# Sheet1.net
KiCad netlist of a schematic drawn in Altium Designer
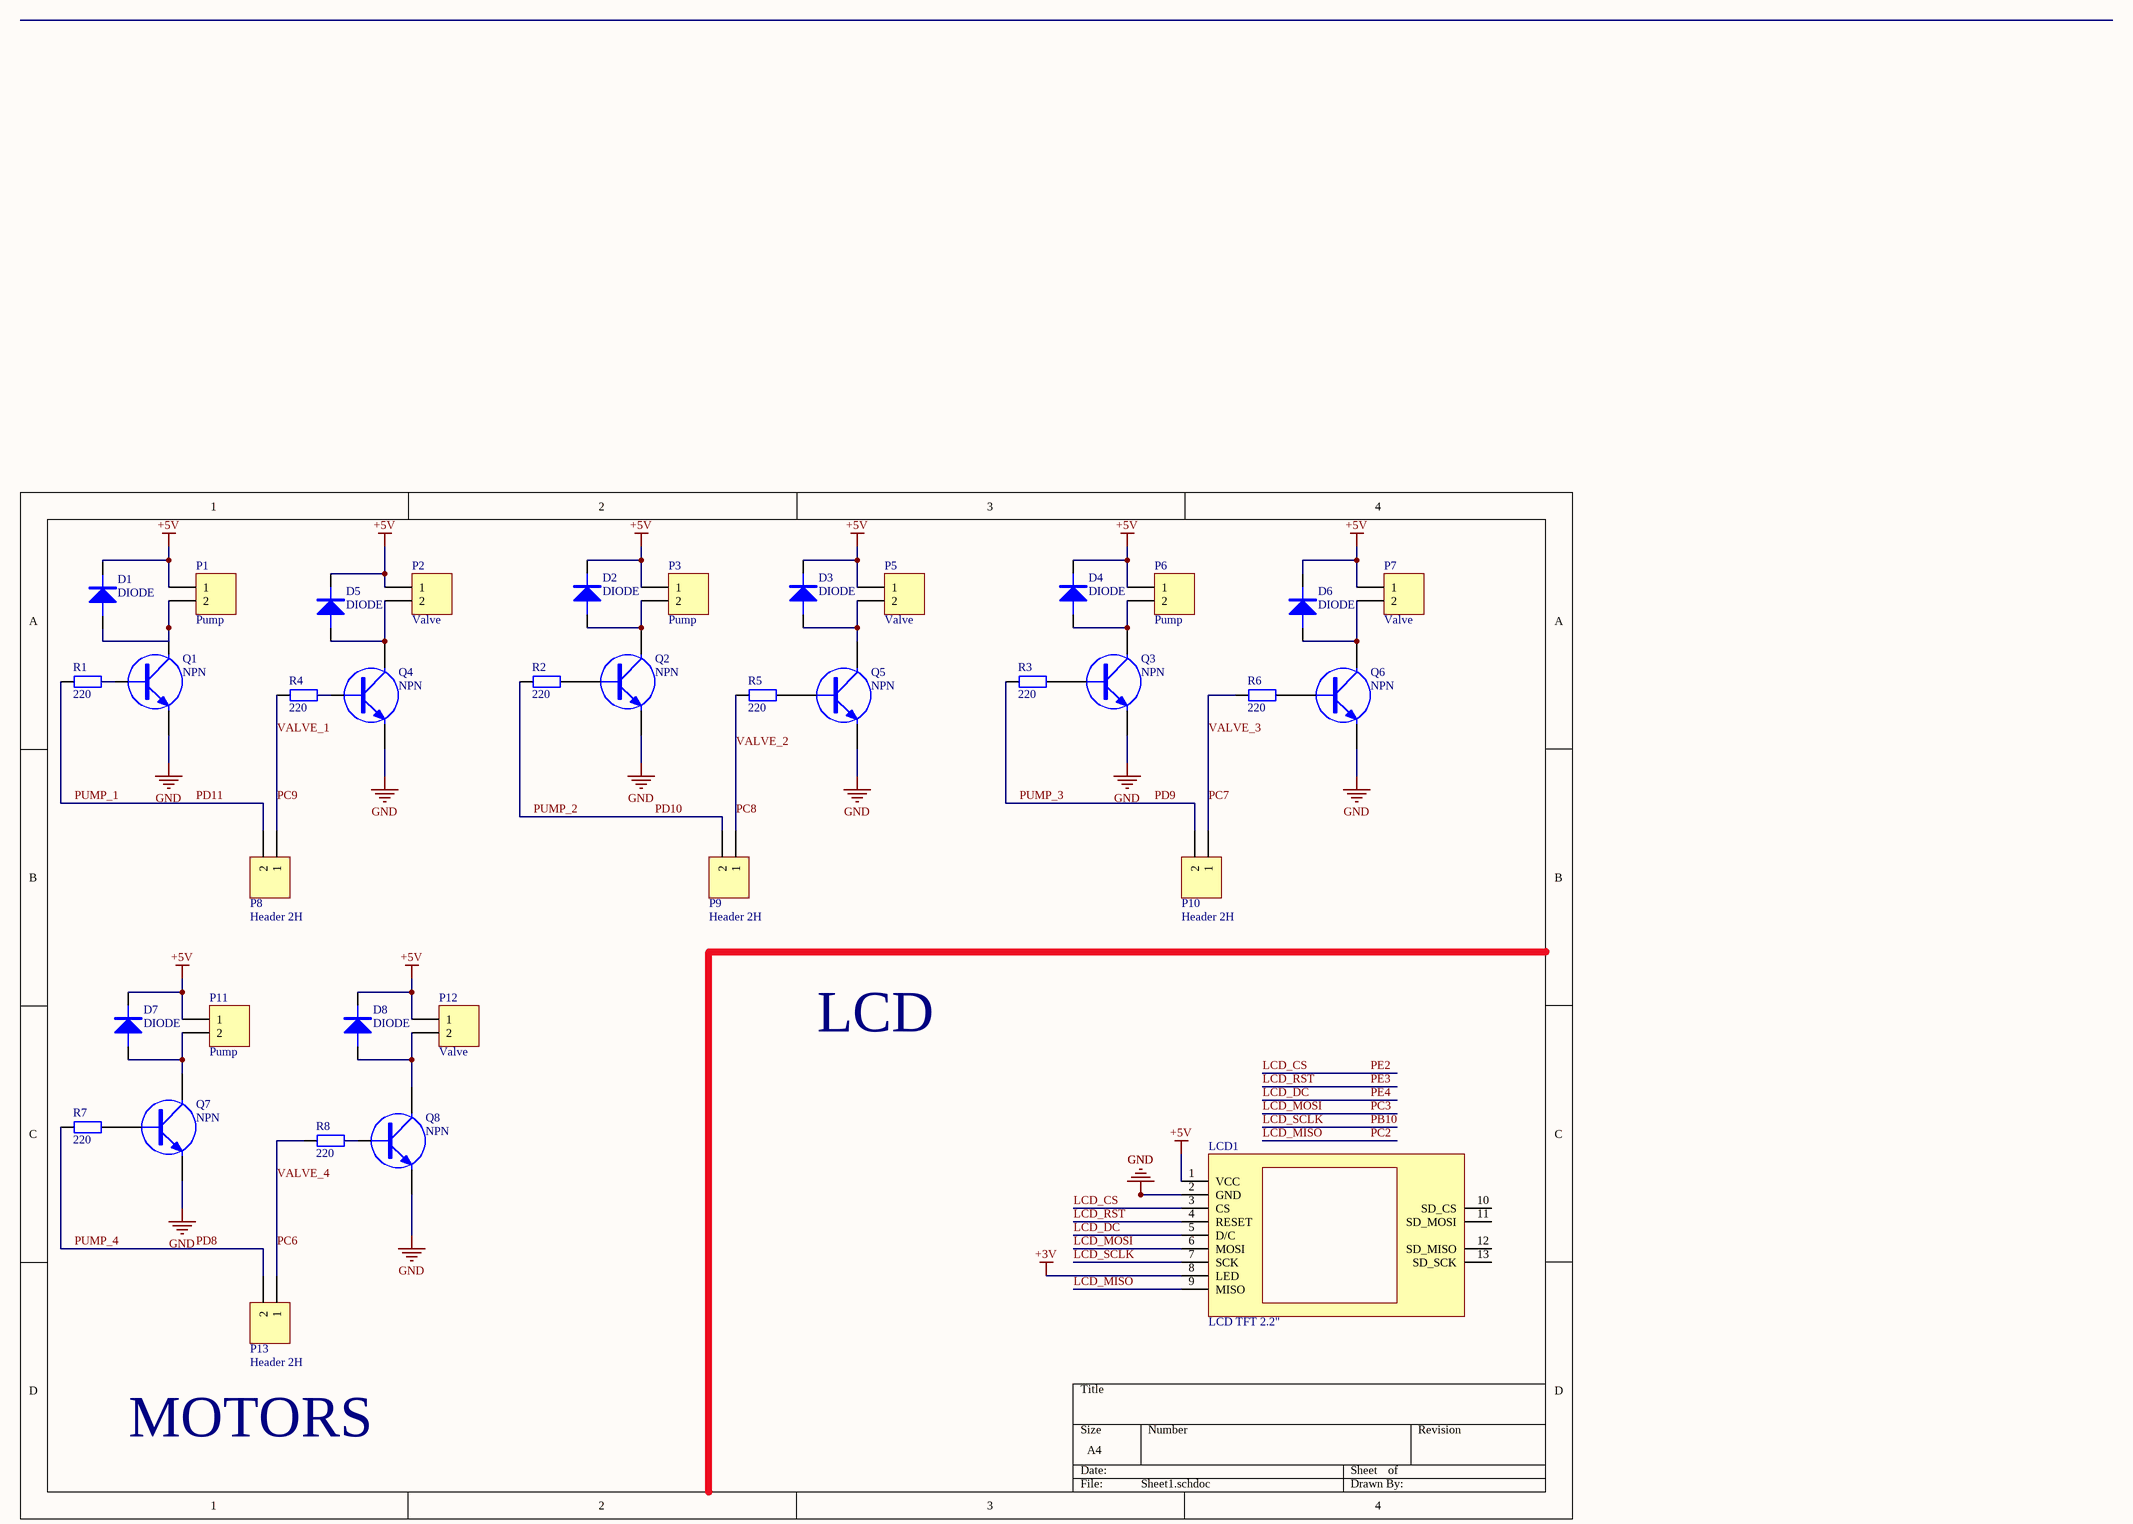
[diagram p0: Sheet1.schdoc]

(export (version "E")
  (design (tool "Eeschema 10.0.6"))
  (components
    (comp (ref "D1")
      (value "DIODE")
      (footprint "DIODE SMA")
      (libsource (lib "ThinhNguyenLib") (part "DIODE"))
    )
    (comp (ref "D2")
      (value "DIODE")
      (footprint "DIODE SMA")
      (libsource (lib "ThinhNguyenLib") (part "DIODE"))
    )
    (comp (ref "D3")
      (value "DIODE")
      (footprint "DIODE SMA")
      (libsource (lib "ThinhNguyenLib") (part "DIODE"))
    )
    (comp (ref "D4")
      (value "DIODE")
      (footprint "DIODE SMA")
      (libsource (lib "ThinhNguyenLib") (part "DIODE"))
    )
    (comp (ref "D5")
      (value "DIODE")
      (footprint "DIODE SMA")
      (libsource (lib "ThinhNguyenLib") (part "DIODE"))
    )
    (comp (ref "D6")
      (value "DIODE")
      (footprint "DIODE SMA")
      (libsource (lib "ThinhNguyenLib") (part "DIODE"))
    )
    (comp (ref "D7")
      (value "DIODE")
      (footprint "DIODE SMA")
      (libsource (lib "ThinhNguyenLib") (part "DIODE"))
    )
    (comp (ref "D8")
      (value "DIODE")
      (footprint "DIODE SMA")
      (libsource (lib "ThinhNguyenLib") (part "DIODE"))
    )
    (comp (ref "LCD1")
      (value "LCD TFT 2.2\"")
      (footprint "LCD TFT 2.2\"")
      (libsource (lib "ThinhNguyenLib") (part "LCD TFT 2.2{dblquote}"))
    )
    (comp (ref "P1")
      (value "Pump")
      (footprint "HDR1X2")
      (fields (field (name "PUBLISHER") "Altium Limited"))
      (libsource (lib "ThinhNguyenLib") (part "Header 2H"))
    )
    (comp (ref "P2")
      (value "Valve")
      (footprint "HDR1X2")
      (fields (field (name "PUBLISHER") "Altium Limited"))
      (libsource (lib "ThinhNguyenLib") (part "Header 2H"))
    )
    (comp (ref "P3")
      (value "Pump")
      (footprint "HDR1X2")
      (fields (field (name "PUBLISHER") "Altium Limited"))
      (libsource (lib "ThinhNguyenLib") (part "Header 2H"))
    )
    (comp (ref "P5")
      (value "Valve")
      (footprint "HDR1X2")
      (fields (field (name "PUBLISHER") "Altium Limited"))
      (libsource (lib "ThinhNguyenLib") (part "Header 2H"))
    )
    (comp (ref "P6")
      (value "Pump")
      (footprint "HDR1X2")
      (fields (field (name "PUBLISHER") "Altium Limited"))
      (libsource (lib "ThinhNguyenLib") (part "Header 2H"))
    )
    (comp (ref "P7")
      (value "Valve")
      (footprint "HDR1X2")
      (fields (field (name "PUBLISHER") "Altium Limited"))
      (libsource (lib "ThinhNguyenLib") (part "Header 2H"))
    )
    (comp (ref "P8")
      (value "Header 2H")
      (footprint "HDR1X2")
      (fields (field (name "PUBLISHER") "Altium Limited"))
      (libsource (lib "") (part "Header 2H_1"))
    )
    (comp (ref "P9")
      (value "Header 2H")
      (footprint "HDR1X2")
      (fields (field (name "PUBLISHER") "Altium Limited"))
      (libsource (lib "") (part "Header 2H_1"))
    )
    (comp (ref "P10")
      (value "Header 2H")
      (footprint "HDR1X2")
      (fields (field (name "PUBLISHER") "Altium Limited"))
      (libsource (lib "") (part "Header 2H_1"))
    )
    (comp (ref "P11")
      (value "Pump")
      (footprint "HDR1X2")
      (fields (field (name "PUBLISHER") "Altium Limited"))
      (libsource (lib "ThinhNguyenLib") (part "Header 2H"))
    )
    (comp (ref "P12")
      (value "Valve")
      (footprint "HDR1X2")
      (fields (field (name "PUBLISHER") "Altium Limited"))
      (libsource (lib "ThinhNguyenLib") (part "Header 2H"))
    )
    (comp (ref "P13")
      (value "Header 2H")
      (footprint "HDR1X2")
      (fields (field (name "PUBLISHER") "Altium Limited"))
      (libsource (lib "") (part "Header 2H_1"))
    )
    (comp (ref "Q1") (value "NPN") (footprint "SOT23 - 3PIN") (libsource (lib "ThinhNguyenLib") (part "NPN")))
    (comp (ref "Q2") (value "NPN") (footprint "SOT23 - 3PIN") (libsource (lib "ThinhNguyenLib") (part "NPN")))
    (comp (ref "Q3") (value "NPN") (footprint "SOT23 - 3PIN") (libsource (lib "ThinhNguyenLib") (part "NPN")))
    (comp (ref "Q4") (value "NPN") (footprint "SOT23 - 3PIN") (libsource (lib "ThinhNguyenLib") (part "NPN")))
    (comp (ref "Q5") (value "NPN") (footprint "SOT23 - 3PIN") (libsource (lib "ThinhNguyenLib") (part "NPN")))
    (comp (ref "Q6") (value "NPN") (footprint "SOT23 - 3PIN") (libsource (lib "ThinhNguyenLib") (part "NPN")))
    (comp (ref "Q7") (value "NPN") (footprint "SOT23 - 3PIN") (libsource (lib "ThinhNguyenLib") (part "NPN")))
    (comp (ref "Q8") (value "NPN") (footprint "SOT23 - 3PIN") (libsource (lib "ThinhNguyenLib") (part "NPN")))
    (comp (ref "R1")
      (value "220")
      (footprint "0805 RESISTOR")
      (libsource (lib "ThinhNguyenLib") (part "RESISTOR"))
    )
    (comp (ref "R2")
      (value "220")
      (footprint "0805 RESISTOR")
      (libsource (lib "ThinhNguyenLib") (part "RESISTOR"))
    )
    (comp (ref "R3")
      (value "220")
      (footprint "0805 RESISTOR")
      (libsource (lib "ThinhNguyenLib") (part "RESISTOR"))
    )
    (comp (ref "R4")
      (value "220")
      (footprint "0805 RESISTOR")
      (libsource (lib "ThinhNguyenLib") (part "RESISTOR"))
    )
    (comp (ref "R5")
      (value "220")
      (footprint "0805 RESISTOR")
      (libsource (lib "ThinhNguyenLib") (part "RESISTOR"))
    )
    (comp (ref "R6")
      (value "220")
      (footprint "0805 RESISTOR")
      (libsource (lib "ThinhNguyenLib") (part "RESISTOR"))
    )
    (comp (ref "R7")
      (value "220")
      (footprint "0805 RESISTOR")
      (libsource (lib "ThinhNguyenLib") (part "RESISTOR"))
    )
    (comp (ref "R8")
      (value "220")
      (footprint "0805 RESISTOR")
      (libsource (lib "ThinhNguyenLib") (part "RESISTOR"))
    )
  )
  (nets
    (net (code "1") (name "+3V") (class "Default")
      (node (ref "LCD1") (pin "8") (pinfunction "LED_8") (pintype "passive"))
    )
    (net (code "2") (name "+5V") (class "Default")
      (node (ref "D1") (pin "2") (pinfunction "2_2") (pintype "passive"))
      (node (ref "D2") (pin "2") (pinfunction "2_2") (pintype "passive"))
      (node (ref "D3") (pin "2") (pinfunction "2_2") (pintype "passive"))
      (node (ref "D4") (pin "2") (pinfunction "2_2") (pintype "passive"))
      (node (ref "D5") (pin "2") (pinfunction "2_2") (pintype "passive"))
      (node (ref "D6") (pin "2") (pinfunction "2_2") (pintype "passive"))
      (node (ref "D7") (pin "2") (pinfunction "2_2") (pintype "passive"))
      (node (ref "D8") (pin "2") (pinfunction "2_2") (pintype "passive"))
      (node (ref "LCD1") (pin "1") (pinfunction "VCC_1") (pintype "passive"))
      (node (ref "P1") (pin "1") (pinfunction "1_1") (pintype "passive"))
      (node (ref "P11") (pin "1") (pinfunction "1_1") (pintype "passive"))
      (node (ref "P12") (pin "1") (pinfunction "1_1") (pintype "passive"))
      (node (ref "P2") (pin "1") (pinfunction "1_1") (pintype "passive"))
      (node (ref "P3") (pin "1") (pinfunction "1_1") (pintype "passive"))
      (node (ref "P5") (pin "1") (pinfunction "1_1") (pintype "passive"))
      (node (ref "P6") (pin "1") (pinfunction "1_1") (pintype "passive"))
      (node (ref "P7") (pin "1") (pinfunction "1_1") (pintype "passive"))
    )
    (net (code "3") (name "/LCD_CS") (class "Default")
      (node (ref "LCD1") (pin "3") (pinfunction "CS_3") (pintype "passive"))
    )
    (net (code "4") (name "/LCD_DC") (class "Default")
      (node (ref "LCD1") (pin "5") (pinfunction "D/C_5") (pintype "passive"))
    )
    (net (code "5") (name "/LCD_MISO") (class "Default")
      (node (ref "LCD1") (pin "9") (pinfunction "MISO_9") (pintype "passive"))
    )
    (net (code "6") (name "/LCD_MOSI") (class "Default")
      (node (ref "LCD1") (pin "6") (pinfunction "MOSI_6") (pintype "passive"))
    )
    (net (code "7") (name "/LCD_RST") (class "Default")
      (node (ref "LCD1") (pin "4") (pinfunction "RESET_4") (pintype "passive"))
    )
    (net (code "8") (name "/LCD_SCLK") (class "Default")
      (node (ref "LCD1") (pin "7") (pinfunction "SCK_7") (pintype "passive"))
    )
    (net (code "9") (name "/PC6") (class "Default")
      (node (ref "P13") (pin "1") (pinfunction "1_1") (pintype "passive"))
      (node (ref "R8") (pin "2") (pinfunction "2_2") (pintype "passive"))
    )
    (net (code "10") (name "/PC7") (class "Default")
      (node (ref "P10") (pin "1") (pinfunction "1_1") (pintype "passive"))
      (node (ref "R6") (pin "2") (pinfunction "2_2") (pintype "passive"))
    )
    (net (code "11") (name "/PC8") (class "Default")
      (node (ref "P9") (pin "1") (pinfunction "1_1") (pintype "passive"))
      (node (ref "R5") (pin "2") (pinfunction "2_2") (pintype "passive"))
    )
    (net (code "12") (name "/PC9") (class "Default")
      (node (ref "P8") (pin "1") (pinfunction "1_1") (pintype "passive"))
      (node (ref "R4") (pin "2") (pinfunction "2_2") (pintype "passive"))
    )
    (net (code "13") (name "/PD8") (class "Default")
      (node (ref "P13") (pin "2") (pinfunction "2_2") (pintype "passive"))
      (node (ref "R7") (pin "2") (pinfunction "2_2") (pintype "passive"))
    )
    (net (code "14") (name "/PD9") (class "Default")
      (node (ref "P10") (pin "2") (pinfunction "2_2") (pintype "passive"))
      (node (ref "R3") (pin "2") (pinfunction "2_2") (pintype "passive"))
    )
    (net (code "15") (name "/PD10") (class "Default")
      (node (ref "P9") (pin "2") (pinfunction "2_2") (pintype "passive"))
      (node (ref "R2") (pin "2") (pinfunction "2_2") (pintype "passive"))
    )
    (net (code "16") (name "/PD11") (class "Default")
      (node (ref "P8") (pin "2") (pinfunction "2_2") (pintype "passive"))
      (node (ref "R1") (pin "2") (pinfunction "2_2") (pintype "passive"))
    )
    (net (code "17") (name "GND") (class "Default")
      (node (ref "LCD1") (pin "2") (pinfunction "GND_2") (pintype "passive"))
      (node (ref "Q1") (pin "1") (pinfunction "E_1") (pintype "passive"))
      (node (ref "Q2") (pin "1") (pinfunction "E_1") (pintype "passive"))
      (node (ref "Q3") (pin "1") (pinfunction "E_1") (pintype "passive"))
      (node (ref "Q4") (pin "1") (pinfunction "E_1") (pintype "passive"))
      (node (ref "Q5") (pin "1") (pinfunction "E_1") (pintype "passive"))
      (node (ref "Q6") (pin "1") (pinfunction "E_1") (pintype "passive"))
      (node (ref "Q7") (pin "1") (pinfunction "E_1") (pintype "passive"))
      (node (ref "Q8") (pin "1") (pinfunction "E_1") (pintype "passive"))
    )
    (net (code "18") (name "Net-(Q1-B)") (class "Default")
      (node (ref "Q1") (pin "3") (pinfunction "B_3") (pintype "passive"))
      (node (ref "R1") (pin "1") (pinfunction "1_1") (pintype "passive"))
    )
    (net (code "19") (name "Net-(Q1-C)") (class "Default")
      (node (ref "D1") (pin "1") (pinfunction "1_1") (pintype "passive"))
      (node (ref "P1") (pin "2") (pinfunction "2_2") (pintype "passive"))
      (node (ref "Q1") (pin "2") (pinfunction "C_2") (pintype "passive"))
    )
    (net (code "20") (name "Net-(Q2-B)") (class "Default")
      (node (ref "Q2") (pin "3") (pinfunction "B_3") (pintype "passive"))
      (node (ref "R2") (pin "1") (pinfunction "1_1") (pintype "passive"))
    )
    (net (code "21") (name "Net-(Q2-C)") (class "Default")
      (node (ref "D2") (pin "1") (pinfunction "1_1") (pintype "passive"))
      (node (ref "P3") (pin "2") (pinfunction "2_2") (pintype "passive"))
      (node (ref "Q2") (pin "2") (pinfunction "C_2") (pintype "passive"))
    )
    (net (code "22") (name "Net-(Q3-B)") (class "Default")
      (node (ref "Q3") (pin "3") (pinfunction "B_3") (pintype "passive"))
      (node (ref "R3") (pin "1") (pinfunction "1_1") (pintype "passive"))
    )
    (net (code "23") (name "Net-(Q3-C)") (class "Default")
      (node (ref "D4") (pin "1") (pinfunction "1_1") (pintype "passive"))
      (node (ref "P6") (pin "2") (pinfunction "2_2") (pintype "passive"))
      (node (ref "Q3") (pin "2") (pinfunction "C_2") (pintype "passive"))
    )
    (net (code "24") (name "Net-(Q4-B)") (class "Default")
      (node (ref "Q4") (pin "3") (pinfunction "B_3") (pintype "passive"))
      (node (ref "R4") (pin "1") (pinfunction "1_1") (pintype "passive"))
    )
    (net (code "25") (name "Net-(Q4-C)") (class "Default")
      (node (ref "D5") (pin "1") (pinfunction "1_1") (pintype "passive"))
      (node (ref "P2") (pin "2") (pinfunction "2_2") (pintype "passive"))
      (node (ref "Q4") (pin "2") (pinfunction "C_2") (pintype "passive"))
    )
    (net (code "26") (name "Net-(Q5-B)") (class "Default")
      (node (ref "Q5") (pin "3") (pinfunction "B_3") (pintype "passive"))
      (node (ref "R5") (pin "1") (pinfunction "1_1") (pintype "passive"))
    )
    (net (code "27") (name "Net-(Q5-C)") (class "Default")
      (node (ref "D3") (pin "1") (pinfunction "1_1") (pintype "passive"))
      (node (ref "P5") (pin "2") (pinfunction "2_2") (pintype "passive"))
      (node (ref "Q5") (pin "2") (pinfunction "C_2") (pintype "passive"))
    )
    (net (code "28") (name "Net-(Q6-B)") (class "Default")
      (node (ref "Q6") (pin "3") (pinfunction "B_3") (pintype "passive"))
      (node (ref "R6") (pin "1") (pinfunction "1_1") (pintype "passive"))
    )
    (net (code "29") (name "Net-(Q6-C)") (class "Default")
      (node (ref "D6") (pin "1") (pinfunction "1_1") (pintype "passive"))
      (node (ref "P7") (pin "2") (pinfunction "2_2") (pintype "passive"))
      (node (ref "Q6") (pin "2") (pinfunction "C_2") (pintype "passive"))
    )
    (net (code "30") (name "Net-(Q7-B)") (class "Default")
      (node (ref "Q7") (pin "3") (pinfunction "B_3") (pintype "passive"))
      (node (ref "R7") (pin "1") (pinfunction "1_1") (pintype "passive"))
    )
    (net (code "31") (name "Net-(Q7-C)") (class "Default")
      (node (ref "D7") (pin "1") (pinfunction "1_1") (pintype "passive"))
      (node (ref "P11") (pin "2") (pinfunction "2_2") (pintype "passive"))
      (node (ref "Q7") (pin "2") (pinfunction "C_2") (pintype "passive"))
    )
    (net (code "32") (name "Net-(Q8-B)") (class "Default")
      (node (ref "Q8") (pin "3") (pinfunction "B_3") (pintype "passive"))
      (node (ref "R8") (pin "1") (pinfunction "1_1") (pintype "passive"))
    )
    (net (code "33") (name "Net-(Q8-C)") (class "Default")
      (node (ref "D8") (pin "1") (pinfunction "1_1") (pintype "passive"))
      (node (ref "P12") (pin "2") (pinfunction "2_2") (pintype "passive"))
      (node (ref "Q8") (pin "2") (pinfunction "C_2") (pintype "passive"))
    )
    (net (code "34") (name "unconnected-(LCD1-SD_CS-Pad10)") (class "Default")
      (node (ref "LCD1") (pin "10") (pinfunction "SD_CS_10") (pintype "passive"))
    )
    (net (code "35") (name "unconnected-(LCD1-SD_MISO-Pad12)") (class "Default")
      (node (ref "LCD1") (pin "12") (pinfunction "SD_MISO_12") (pintype "passive"))
    )
    (net (code "36") (name "unconnected-(LCD1-SD_MOSI-Pad11)") (class "Default")
      (node (ref "LCD1") (pin "11") (pinfunction "SD_MOSI_11") (pintype "passive"))
    )
    (net (code "37") (name "unconnected-(LCD1-SD_SCK-Pad13)") (class "Default")
      (node (ref "LCD1") (pin "13") (pinfunction "SD_SCK_13") (pintype "passive"))
    )
  )
)
